# Low_voltage_motor_driver_v2.net
KiCad netlist of a schematic drawn in EAGLE
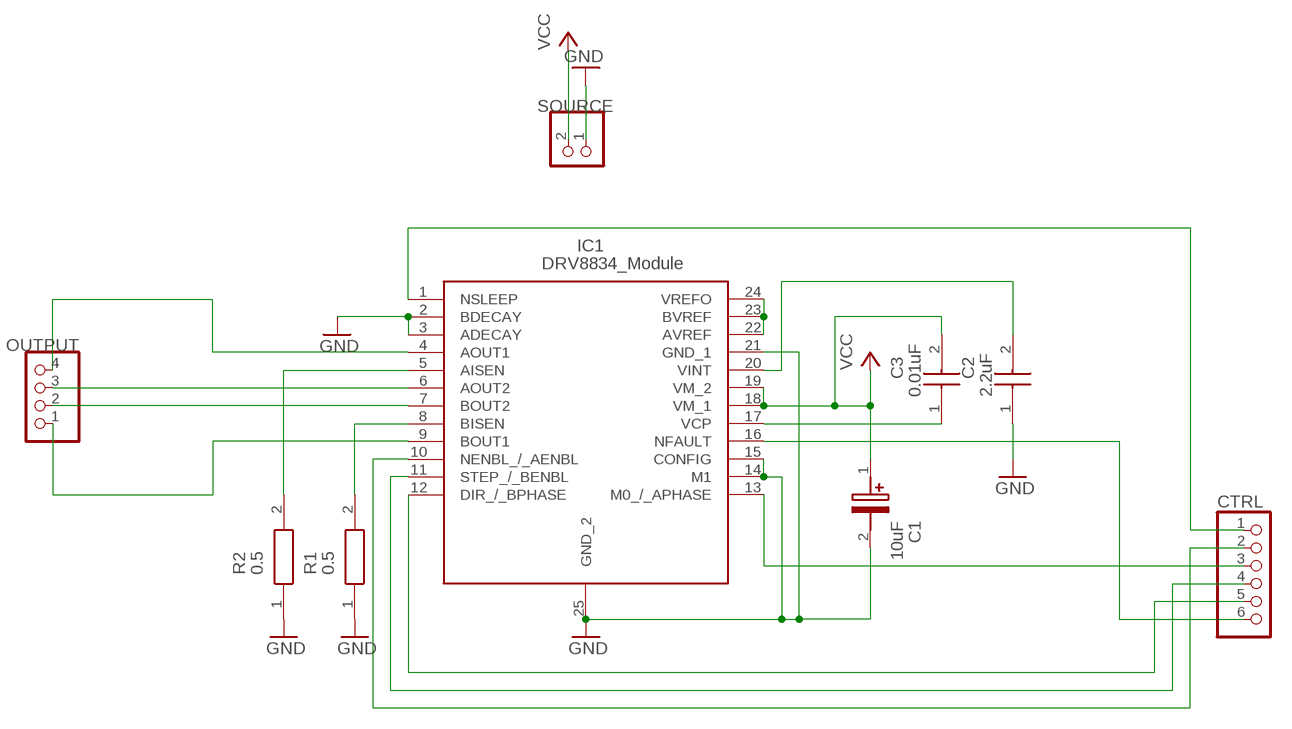
[diagram p0: schematic, sheet 1]

(export (version "E")
  (design (tool "Eeschema 10.0.6"))
  (components
    (comp (ref "C1")
      (value "10uF")
      (footprint "eagle-import:CAPPRD200W50D500H1250")
      (fields
        (field (name "MANUFACTURER_PART_NUMBER") "ESL106M050AC3AA")
        (field (name "MOUSER_PART_NUMBER") "80-ESL106M050AC3AA")
      )
      (libsource (lib "eagle-import") (part "ESL106M050AC3AA"))
    )
    (comp (ref "C2")
      (value "2.2uF")
      (footprint "eagle-import:CAPC2012X88N")
      (fields
        (field (name "MANUFACTURER_PART_NUMBER") "C0805C103J4RECAUTO7210")
        (field (name "MOUSER_PART_NUMBER") "80-C0805C103J4REAULR")
      )
      (libsource (lib "eagle-import") (part "C0805C103J4RECAUTO7210"))
    )
    (comp (ref "C3")
      (value "0.01uF")
      (footprint "eagle-import:CAPC2012X88N")
      (fields
        (field (name "MANUFACTURER_PART_NUMBER") "C0805C103J4RECAUTO7210")
        (field (name "MOUSER_PART_NUMBER") "80-C0805C103J4REAULR")
      )
      (libsource (lib "eagle-import") (part "C0805C103J4RECAUTO7210"))
    )
    (comp (ref "CTRL")
      (value "PINHD-1X6")
      (footprint "eagle-import:1X06")
      (libsource (lib "eagle-import") (part "PINHD-1X6"))
    )
    (comp (ref "IC1")
      (value "DRV8834_Module")
      (footprint "eagle-import:SOP65P640X120-25N")
      (fields
        (field (name "MANUFACTURER_PART_NUMBER") "DRV8834PWPR")
        (field (name "MOUSER_PART_NUMBER") "595-DRV8834PWPR")
      )
      (libsource (lib "eagle-import") (part "DRV8834PWPR"))
    )
    (comp (ref "OUTPUT")
      (value "PINHD-1X4")
      (footprint "eagle-import:1X04")
      (libsource (lib "eagle-import") (part "PINHD-1X4"))
    )
    (comp (ref "R1")
      (value "0.5")
      (footprint "eagle-import:RESC5125X89N")
      (fields (field (name "MANUFACTURER_PART_NUMBER") "WSL2010R2000DEA"))
      (libsource (lib "eagle-import") (part "WSL2010R2000DEA"))
    )
    (comp (ref "R2")
      (value "0.5")
      (footprint "eagle-import:RESC5125X89N")
      (fields (field (name "MANUFACTURER_PART_NUMBER") "WSL2010R2000DEA"))
      (libsource (lib "eagle-import") (part "WSL2010R2000DEA"))
    )
    (comp (ref "SOURCE")
      (value "PINHD-1X2")
      (footprint "eagle-import:1X02")
      (libsource (lib "eagle-import") (part "PINHD-1X2"))
    )
  )
  (nets
    (net (code "1") (name "GND") (class "Default")
      (node (ref "C1") (pin "2") (pinfunction "-_2") (pintype "bidirectional"))
      (node (ref "C2") (pin "1") (pinfunction "1_1") (pintype "bidirectional"))
      (node (ref "IC1") (pin "14") (pinfunction "M1_14") (pintype "bidirectional"))
      (node (ref "IC1") (pin "15") (pinfunction "CONFIG_15") (pintype "bidirectional"))
      (node (ref "IC1") (pin "2") (pinfunction "BDECAY_2") (pintype "bidirectional"))
      (node (ref "IC1") (pin "21") (pinfunction "GND_1_21") (pintype "bidirectional"))
      (node (ref "IC1") (pin "25") (pinfunction "GND_2_25") (pintype "bidirectional"))
      (node (ref "IC1") (pin "3") (pinfunction "ADECAY_3") (pintype "bidirectional"))
      (node (ref "R1") (pin "1") (pinfunction "1_1") (pintype "bidirectional"))
      (node (ref "R2") (pin "1") (pinfunction "1_1") (pintype "bidirectional"))
      (node (ref "SOURCE") (pin "1") (pinfunction "1_1") (pintype "passive"))
    )
    (net (code "2") (name "Net-(IC1-AISEN)") (class "Default")
      (node (ref "IC1") (pin "5") (pinfunction "AISEN_5") (pintype "bidirectional"))
      (node (ref "R2") (pin "2") (pinfunction "2_2") (pintype "bidirectional"))
    )
    (net (code "3") (name "Net-(IC1-AOUT1)") (class "Default")
      (node (ref "IC1") (pin "4") (pinfunction "AOUT1_4") (pintype "bidirectional"))
      (node (ref "OUTPUT") (pin "4") (pinfunction "4_4") (pintype "passive"))
    )
    (net (code "4") (name "Net-(IC1-AOUT2)") (class "Default")
      (node (ref "IC1") (pin "6") (pinfunction "AOUT2_6") (pintype "bidirectional"))
      (node (ref "OUTPUT") (pin "3") (pinfunction "3_3") (pintype "passive"))
    )
    (net (code "5") (name "Net-(IC1-AVREF)") (class "Default")
      (node (ref "IC1") (pin "22") (pinfunction "AVREF_22") (pintype "bidirectional"))
      (node (ref "IC1") (pin "23") (pinfunction "BVREF_23") (pintype "bidirectional"))
      (node (ref "IC1") (pin "24") (pinfunction "VREFO_24") (pintype "bidirectional"))
    )
    (net (code "6") (name "Net-(IC1-BISEN)") (class "Default")
      (node (ref "IC1") (pin "8") (pinfunction "BISEN_8") (pintype "bidirectional"))
      (node (ref "R1") (pin "2") (pinfunction "2_2") (pintype "bidirectional"))
    )
    (net (code "7") (name "Net-(IC1-BOUT1)") (class "Default")
      (node (ref "IC1") (pin "9") (pinfunction "BOUT1_9") (pintype "bidirectional"))
      (node (ref "OUTPUT") (pin "1") (pinfunction "1_1") (pintype "passive"))
    )
    (net (code "8") (name "Net-(IC1-BOUT2)") (class "Default")
      (node (ref "IC1") (pin "7") (pinfunction "BOUT2_7") (pintype "bidirectional"))
      (node (ref "OUTPUT") (pin "2") (pinfunction "2_2") (pintype "passive"))
    )
    (net (code "9") (name "Net-(IC1-DIR_{slash}_BPHASE)") (class "Default")
      (node (ref "CTRL") (pin "5") (pinfunction "5_5") (pintype "passive"))
      (node (ref "IC1") (pin "12") (pinfunction "DIR_/_BPHASE_12") (pintype "bidirectional"))
    )
    (net (code "10") (name "Net-(IC1-M0_{slash}_APHASE)") (class "Default")
      (node (ref "CTRL") (pin "3") (pinfunction "3_3") (pintype "passive"))
      (node (ref "IC1") (pin "13") (pinfunction "M0_/_APHASE_13") (pintype "bidirectional"))
    )
    (net (code "11") (name "Net-(IC1-NENBL_{slash}_AENBL)") (class "Default")
      (node (ref "CTRL") (pin "2") (pinfunction "2_2") (pintype "passive"))
      (node (ref "IC1") (pin "10") (pinfunction "NENBL_/_AENBL_10") (pintype "bidirectional"))
    )
    (net (code "12") (name "Net-(IC1-NFAULT)") (class "Default")
      (node (ref "CTRL") (pin "6") (pinfunction "6_6") (pintype "passive"))
      (node (ref "IC1") (pin "16") (pinfunction "NFAULT_16") (pintype "bidirectional"))
    )
    (net (code "13") (name "Net-(IC1-NSLEEP)") (class "Default")
      (node (ref "CTRL") (pin "1") (pinfunction "1_1") (pintype "passive"))
      (node (ref "IC1") (pin "1") (pinfunction "NSLEEP_1") (pintype "bidirectional"))
    )
    (net (code "14") (name "Net-(IC1-STEP_{slash}_BENBL)") (class "Default")
      (node (ref "CTRL") (pin "4") (pinfunction "4_4") (pintype "passive"))
      (node (ref "IC1") (pin "11") (pinfunction "STEP_/_BENBL_11") (pintype "bidirectional"))
    )
    (net (code "15") (name "Net-(IC1-VCP)") (class "Default")
      (node (ref "C3") (pin "1") (pinfunction "1_1") (pintype "bidirectional"))
      (node (ref "IC1") (pin "17") (pinfunction "VCP_17") (pintype "bidirectional"))
    )
    (net (code "16") (name "Net-(IC1-VINT)") (class "Default")
      (node (ref "C2") (pin "2") (pinfunction "2_2") (pintype "bidirectional"))
      (node (ref "IC1") (pin "20") (pinfunction "VINT_20") (pintype "bidirectional"))
    )
    (net (code "17") (name "VCC") (class "Default")
      (node (ref "C1") (pin "1") (pinfunction "+_1") (pintype "bidirectional"))
      (node (ref "C3") (pin "2") (pinfunction "2_2") (pintype "bidirectional"))
      (node (ref "IC1") (pin "18") (pinfunction "VM_1_18") (pintype "bidirectional"))
      (node (ref "IC1") (pin "19") (pinfunction "VM_2_19") (pintype "bidirectional"))
      (node (ref "SOURCE") (pin "2") (pinfunction "2_2") (pintype "passive"))
    )
  )
)
